# TB_Motor_driver_pcb.net
KiCad netlist of a schematic drawn in Altium Designer
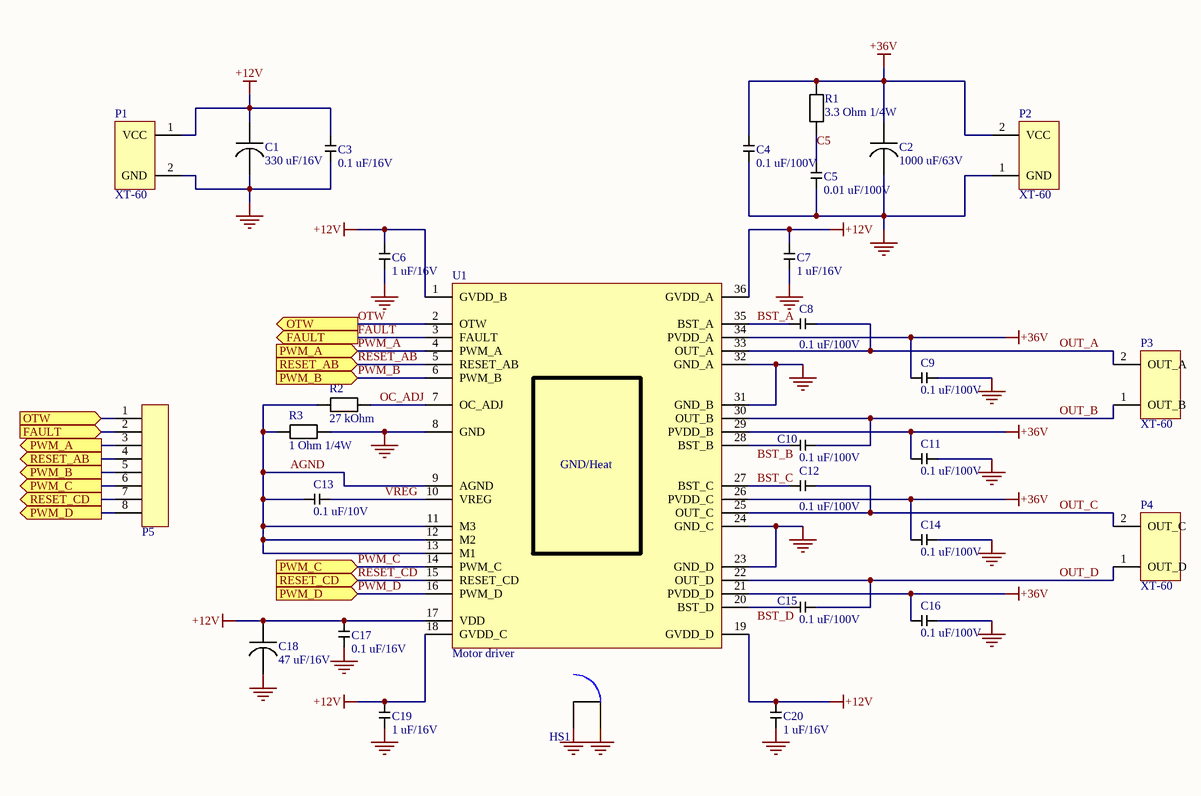
[diagram p0: TB Motor driver pcb.SchDoc]

(export (version "E")
  (design (tool "Eeschema 10.0.6"))
  (components
    (comp (ref "C1")
      (value "330 uF/16V")
      (footprint "C_EL_SMT_Ø10")
      (fields (field (name "Comment") "C_EL_SMT_Ø10"))
      (libsource (lib "FF_component_lib") (part "C_EL_SMT_Ø10"))
    )
    (comp (ref "C2")
      (value "1000 uF/63V")
      (footprint "C_EL_SMT_Ø18")
      (fields (field (name "Comment") "C_EL_SMT_Ø18"))
      (libsource (lib "FF_component_lib") (part "C_EL_SMT_Ø18"))
    )
    (comp (ref "C3")
      (value "0.1 uF/16V")
      (footprint "C_SMD_0805_pcb")
      (fields (field (name "Comment") "SMD"))
      (libsource (lib "FF_component_lib") (part "C_SMD_0805"))
    )
    (comp (ref "C4")
      (value "0.1 uF/100V")
      (footprint "C_SMD_0805_pcb")
      (fields (field (name "Comment") "SMD"))
      (libsource (lib "FF_component_lib") (part "C_SMD_0805"))
    )
    (comp (ref "C5")
      (value "0.01 uF/100V")
      (footprint "C_SMD_0805_pcb")
      (fields (field (name "Comment") "SMD"))
      (libsource (lib "FF_component_lib") (part "C_SMD_0805"))
    )
    (comp (ref "C6")
      (value "1 uF/16V")
      (footprint "C_SMD_0805_pcb")
      (fields (field (name "Comment") "SMD"))
      (libsource (lib "FF_component_lib") (part "C_SMD_0805"))
    )
    (comp (ref "C7")
      (value "1 uF/16V")
      (footprint "C_SMD_0805_pcb")
      (fields (field (name "Comment") "SMD"))
      (libsource (lib "FF_component_lib") (part "C_SMD_0805"))
    )
    (comp (ref "C8")
      (value "0.1 uF/100V")
      (footprint "C_SMD_0805_pcb")
      (fields (field (name "Comment") "SMD"))
      (libsource (lib "FF_component_lib") (part "C_SMD_0805"))
    )
    (comp (ref "C9")
      (value "0.1 uF/100V")
      (footprint "C_SMD_0805_pcb")
      (fields (field (name "Comment") "SMD"))
      (libsource (lib "FF_component_lib") (part "C_SMD_0805"))
    )
    (comp (ref "C10")
      (value "0.1 uF/100V")
      (footprint "C_SMD_0805_pcb")
      (fields (field (name "Comment") "SMD"))
      (libsource (lib "FF_component_lib") (part "C_SMD_0805"))
    )
    (comp (ref "C11")
      (value "0.1 uF/100V")
      (footprint "C_SMD_0805_pcb")
      (fields (field (name "Comment") "SMD"))
      (libsource (lib "FF_component_lib") (part "C_SMD_0805"))
    )
    (comp (ref "C12")
      (value "0.1 uF/100V")
      (footprint "C_SMD_0805_pcb")
      (fields (field (name "Comment") "SMD"))
      (libsource (lib "FF_component_lib") (part "C_SMD_0805"))
    )
    (comp (ref "C13")
      (value "0.1 uF/10V")
      (footprint "C_SMD_0805_pcb")
      (fields (field (name "Comment") "SMD"))
      (libsource (lib "FF_component_lib") (part "C_SMD_0805"))
    )
    (comp (ref "C14")
      (value "0.1 uF/100V")
      (footprint "C_SMD_0805_pcb")
      (fields (field (name "Comment") "SMD"))
      (libsource (lib "FF_component_lib") (part "C_SMD_0805"))
    )
    (comp (ref "C15")
      (value "0.1 uF/100V")
      (footprint "C_SMD_0805_pcb")
      (fields (field (name "Comment") "SMD"))
      (libsource (lib "FF_component_lib") (part "C_SMD_0805"))
    )
    (comp (ref "C16")
      (value "0.1 uF/100V")
      (footprint "C_SMD_0805_pcb")
      (fields (field (name "Comment") "SMD"))
      (libsource (lib "FF_component_lib") (part "C_SMD_0805"))
    )
    (comp (ref "C17")
      (value "0.1 uF/16V")
      (footprint "C_SMD_0805_pcb")
      (fields (field (name "Comment") "SMD"))
      (libsource (lib "FF_component_lib") (part "C_SMD_0805"))
    )
    (comp (ref "C18")
      (value "47 uF/16V")
      (footprint "C_EL_SMT_Ø6.3")
      (fields (field (name "Comment") "C_EL_SMT_Ø6.3"))
      (libsource (lib "FF_component_lib") (part "C_EL_SMT_Ø6.3"))
    )
    (comp (ref "C19")
      (value "1 uF/16V")
      (footprint "C_SMD_0805_pcb")
      (fields (field (name "Comment") "SMD"))
      (libsource (lib "FF_component_lib") (part "C_SMD_0805"))
    )
    (comp (ref "C20")
      (value "1 uF/16V")
      (footprint "C_SMD_0805_pcb")
      (fields (field (name "Comment") "SMD"))
      (libsource (lib "FF_component_lib") (part "C_SMD_0805"))
    )
    (comp (ref "HS1")
      (value "ATS-1042-C1-R0")
      (footprint "HS_TB")
      (description "HEATSINK 41X45X15MM NYLONPUSHPIN")
      (libsource (lib "FF_component_lib") (part "ATS-1042-C1-R0"))
    )
    (comp (ref "P1") (value "XT-60") (footprint "XT-60") (libsource (lib "") (part "XT-60_1")))
    (comp (ref "P2") (value "XT-60") (footprint "XT-60") (libsource (lib "") (part "XT-60_3")))
    (comp (ref "P3") (value "XT-60") (footprint "XT-60") (libsource (lib "") (part "XT-60_2")))
    (comp (ref "P4") (value "XT-60") (footprint "XT-60") (libsource (lib "FF_component_lib") (part "XT-60")))
    (comp (ref "P5")
      (value "JST_SE_8PIN")
      (footprint "JST_SE_8PIN")
      (libsource (lib "FF_component_lib") (part "JST_SE_8PIN"))
    )
    (comp (ref "R1")
      (value "3.3 Ohm 1/4W")
      (footprint "R_SMD_0805_pcb")
      (fields (field (name "Comment") "SMD"))
      (libsource (lib "FF_component_lib") (part "R_SMD_0805"))
    )
    (comp (ref "R2")
      (value "27 kOhm")
      (footprint "R_SMD_0805_pcb")
      (fields (field (name "Comment") "SMD"))
      (libsource (lib "FF_component_lib") (part "R_SMD_0805"))
    )
    (comp (ref "R3")
      (value "1 Ohm 1/4W")
      (footprint "R_SMD_0805_pcb")
      (fields (field (name "Comment") "SMD"))
      (libsource (lib "FF_component_lib") (part "R_SMD_0805"))
    )
    (comp (ref "U1")
      (value "Motor driver")
      (footprint "DRV8432DKDR-SOP36")
      (description "IC BRIDGE DRIVER PAR 36HSSOP")
      (libsource (lib "FF_component_lib") (part "DRV8432DKDR"))
    )
  )
  (nets
    (net (code "1") (name "+12V") (class "Default")
      (node (ref "C1") (pin "2") (pinfunction "18_2") (pintype "passive"))
      (node (ref "C17") (pin "1") (pinfunction "1_1") (pintype "passive"))
      (node (ref "C18") (pin "2") (pinfunction "18_2") (pintype "passive"))
      (node (ref "C19") (pin "1") (pinfunction "1_1") (pintype "passive"))
      (node (ref "C20") (pin "1") (pinfunction "1_1") (pintype "passive"))
      (node (ref "C3") (pin "1") (pinfunction "1_1") (pintype "passive"))
      (node (ref "C6") (pin "2") (pinfunction "2_2") (pintype "passive"))
      (node (ref "C7") (pin "2") (pinfunction "2_2") (pintype "passive"))
      (node (ref "P1") (pin "1") (pinfunction "VCC_1") (pintype "passive"))
      (node (ref "U1") (pin "1") (pinfunction "GVDD_B_1") (pintype "passive"))
      (node (ref "U1") (pin "17") (pinfunction "VDD_17") (pintype "passive"))
      (node (ref "U1") (pin "18") (pinfunction "GVDD_C_18") (pintype "passive"))
      (node (ref "U1") (pin "19") (pinfunction "GVDD_D_19") (pintype "passive"))
      (node (ref "U1") (pin "36") (pinfunction "GVDD_A_36") (pintype "passive"))
    )
    (net (code "2") (name "+36V") (class "Default")
      (node (ref "C11") (pin "2") (pinfunction "2_2") (pintype "passive"))
      (node (ref "C14") (pin "2") (pinfunction "2_2") (pintype "passive"))
      (node (ref "C16") (pin "2") (pinfunction "2_2") (pintype "passive"))
      (node (ref "C2") (pin "2") (pinfunction "18_2") (pintype "passive"))
      (node (ref "C4") (pin "2") (pinfunction "2_2") (pintype "passive"))
      (node (ref "C9") (pin "2") (pinfunction "2_2") (pintype "passive"))
      (node (ref "P2") (pin "2") (pinfunction "VCC_2") (pintype "passive"))
      (node (ref "R1") (pin "2") (pinfunction "2_2") (pintype "passive"))
      (node (ref "U1") (pin "21") (pinfunction "PVDD_D_21") (pintype "passive"))
      (node (ref "U1") (pin "26") (pinfunction "PVDD_C_26") (pintype "passive"))
      (node (ref "U1") (pin "29") (pinfunction "PVDD_B_29") (pintype "passive"))
      (node (ref "U1") (pin "34") (pinfunction "PVDD_A_34") (pintype "passive"))
    )
    (net (code "3") (name "/AGND") (class "Default")
      (node (ref "C13") (pin "2") (pinfunction "2_2") (pintype "passive"))
      (node (ref "R2") (pin "1") (pinfunction "1_1") (pintype "passive"))
      (node (ref "R3") (pin "1") (pinfunction "1_1") (pintype "passive"))
      (node (ref "U1") (pin "11") (pinfunction "M3_11") (pintype "passive"))
      (node (ref "U1") (pin "12") (pinfunction "M2_12") (pintype "passive"))
      (node (ref "U1") (pin "13") (pinfunction "M1_13") (pintype "passive"))
      (node (ref "U1") (pin "9") (pinfunction "AGND_9") (pintype "passive"))
    )
    (net (code "4") (name "/BST_A") (class "Default")
      (node (ref "C8") (pin "2") (pinfunction "2_2") (pintype "passive"))
      (node (ref "U1") (pin "35") (pinfunction "BST_A_35") (pintype "passive"))
    )
    (net (code "5") (name "/BST_B") (class "Default")
      (node (ref "C10") (pin "2") (pinfunction "2_2") (pintype "passive"))
      (node (ref "U1") (pin "28") (pinfunction "BST_B_28") (pintype "passive"))
    )
    (net (code "6") (name "/BST_C") (class "Default")
      (node (ref "C12") (pin "2") (pinfunction "2_2") (pintype "passive"))
      (node (ref "U1") (pin "27") (pinfunction "BST_C_27") (pintype "passive"))
    )
    (net (code "7") (name "/BST_D") (class "Default")
      (node (ref "C15") (pin "2") (pinfunction "2_2") (pintype "passive"))
      (node (ref "U1") (pin "20") (pinfunction "BST_D_20") (pintype "passive"))
    )
    (net (code "8") (name "/C5") (class "Default")
      (node (ref "C5") (pin "1") (pinfunction "1_1") (pintype "passive"))
      (node (ref "R1") (pin "1") (pinfunction "1_1") (pintype "passive"))
    )
    (net (code "9") (name "/FAULT") (class "Default")
      (node (ref "P5") (pin "2") (pinfunction "2_2") (pintype "passive"))
      (node (ref "U1") (pin "3") (pinfunction "FAULT_3") (pintype "passive"))
    )
    (net (code "10") (name "/OC_ADJ") (class "Default")
      (node (ref "R2") (pin "2") (pinfunction "2_2") (pintype "passive"))
      (node (ref "U1") (pin "7") (pinfunction "OC_ADJ_7") (pintype "passive"))
    )
    (net (code "11") (name "/OTW") (class "Default")
      (node (ref "P5") (pin "1") (pinfunction "1_1") (pintype "passive"))
      (node (ref "U1") (pin "2") (pinfunction "OTW_2") (pintype "passive"))
    )
    (net (code "12") (name "/OUT_A") (class "Default")
      (node (ref "C8") (pin "1") (pinfunction "1_1") (pintype "passive"))
      (node (ref "P3") (pin "2") (pinfunction "OUT_A_2") (pintype "passive"))
      (node (ref "U1") (pin "33") (pinfunction "OUT_A_33") (pintype "passive"))
    )
    (net (code "13") (name "/OUT_B") (class "Default")
      (node (ref "C10") (pin "1") (pinfunction "1_1") (pintype "passive"))
      (node (ref "P3") (pin "1") (pinfunction "OUT_B_1") (pintype "passive"))
      (node (ref "U1") (pin "30") (pinfunction "OUT_B_30") (pintype "passive"))
    )
    (net (code "14") (name "/OUT_C") (class "Default")
      (node (ref "C12") (pin "1") (pinfunction "1_1") (pintype "passive"))
      (node (ref "P4") (pin "2") (pinfunction "OUT_C_2") (pintype "passive"))
      (node (ref "U1") (pin "25") (pinfunction "OUT_C_25") (pintype "passive"))
    )
    (net (code "15") (name "/OUT_D") (class "Default")
      (node (ref "C15") (pin "1") (pinfunction "1_1") (pintype "passive"))
      (node (ref "P4") (pin "1") (pinfunction "OUT_D_1") (pintype "passive"))
      (node (ref "U1") (pin "22") (pinfunction "OUT_D_22") (pintype "passive"))
    )
    (net (code "16") (name "/PWM_A") (class "Default")
      (node (ref "P5") (pin "3") (pinfunction "3_3") (pintype "passive"))
      (node (ref "U1") (pin "4") (pinfunction "PWM_A_4") (pintype "passive"))
    )
    (net (code "17") (name "/PWM_B") (class "Default")
      (node (ref "P5") (pin "5") (pinfunction "5_5") (pintype "passive"))
      (node (ref "U1") (pin "6") (pinfunction "PWM_B_6") (pintype "passive"))
    )
    (net (code "18") (name "/PWM_C") (class "Default")
      (node (ref "P5") (pin "6") (pinfunction "6_6") (pintype "passive"))
      (node (ref "U1") (pin "14") (pinfunction "PWM_C_14") (pintype "passive"))
    )
    (net (code "19") (name "/PWM_D") (class "Default")
      (node (ref "P5") (pin "8") (pinfunction "8_8") (pintype "passive"))
      (node (ref "U1") (pin "16") (pinfunction "PWM_D_16") (pintype "passive"))
    )
    (net (code "20") (name "/RESET_AB") (class "Default")
      (node (ref "P5") (pin "4") (pinfunction "4_4") (pintype "passive"))
      (node (ref "U1") (pin "5") (pinfunction "RESET_AB_5") (pintype "passive"))
    )
    (net (code "21") (name "/RESET_CD") (class "Default")
      (node (ref "P5") (pin "7") (pinfunction "7_7") (pintype "passive"))
      (node (ref "U1") (pin "15") (pinfunction "RESET_CD_15") (pintype "passive"))
    )
    (net (code "22") (name "/VREG") (class "Default")
      (node (ref "C13") (pin "1") (pinfunction "1_1") (pintype "passive"))
      (node (ref "U1") (pin "10") (pinfunction "VREG_10") (pintype "passive"))
    )
    (net (code "23") (name "GND") (class "Default")
      (node (ref "C1") (pin "1") (pinfunction "1_1") (pintype "passive"))
      (node (ref "C11") (pin "1") (pinfunction "1_1") (pintype "passive"))
      (node (ref "C14") (pin "1") (pinfunction "1_1") (pintype "passive"))
      (node (ref "C16") (pin "1") (pinfunction "1_1") (pintype "passive"))
      (node (ref "C17") (pin "2") (pinfunction "2_2") (pintype "passive"))
      (node (ref "C18") (pin "1") (pinfunction "1_1") (pintype "passive"))
      (node (ref "C19") (pin "2") (pinfunction "2_2") (pintype "passive"))
      (node (ref "C2") (pin "1") (pinfunction "1_1") (pintype "passive"))
      (node (ref "C20") (pin "2") (pinfunction "2_2") (pintype "passive"))
      (node (ref "C3") (pin "2") (pinfunction "2_2") (pintype "passive"))
      (node (ref "C4") (pin "1") (pinfunction "1_1") (pintype "passive"))
      (node (ref "C5") (pin "2") (pinfunction "2_2") (pintype "passive"))
      (node (ref "C6") (pin "1") (pinfunction "1_1") (pintype "passive"))
      (node (ref "C7") (pin "1") (pinfunction "1_1") (pintype "passive"))
      (node (ref "C9") (pin "1") (pinfunction "1_1") (pintype "passive"))
      (node (ref "HS1") (pin "1") (pinfunction "1_1") (pintype "passive"))
      (node (ref "HS1") (pin "2") (pinfunction "2_2") (pintype "passive"))
      (node (ref "P1") (pin "2") (pinfunction "GND_2") (pintype "passive"))
      (node (ref "P2") (pin "1") (pinfunction "GND_1") (pintype "passive"))
      (node (ref "R3") (pin "2") (pinfunction "2_2") (pintype "passive"))
      (node (ref "U1") (pin "23") (pinfunction "GND_D_23") (pintype "passive"))
      (node (ref "U1") (pin "24") (pinfunction "GND_C_24") (pintype "passive"))
      (node (ref "U1") (pin "31") (pinfunction "GND_B_31") (pintype "passive"))
      (node (ref "U1") (pin "32") (pinfunction "GND_A_32") (pintype "passive"))
      (node (ref "U1") (pin "8") (pinfunction "GND_8") (pintype "passive"))
    )
  )
)
